# W603B.net
KiCad netlist of a schematic drawn in EAGLE
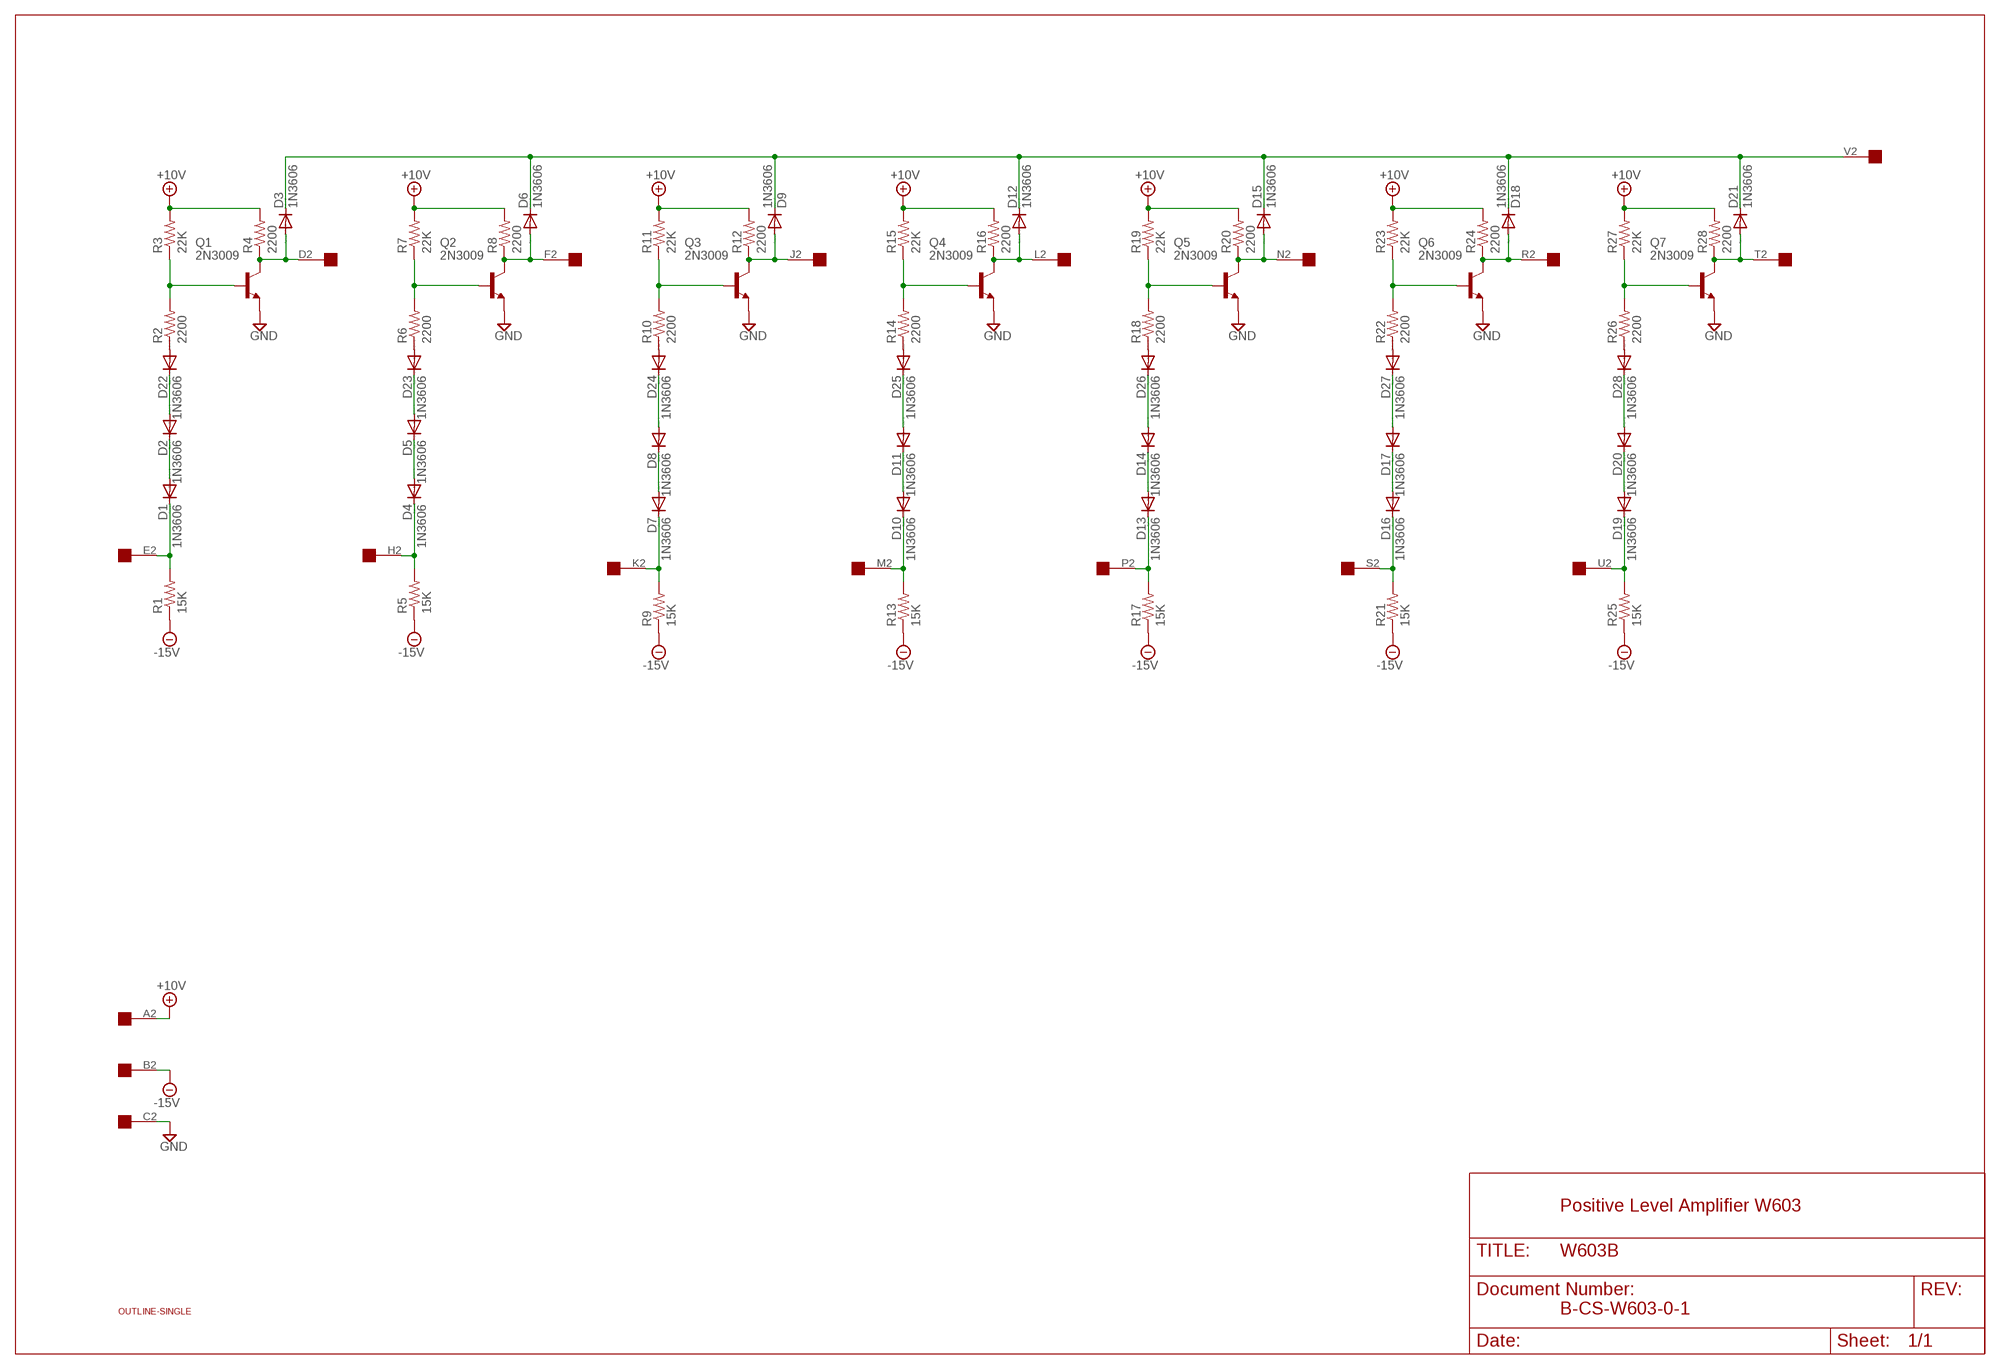
[diagram p0: schematic, sheet 1]

(export (version "E")
  (design (tool "Eeschema 10.0.6"))
  (components
    (comp (ref "D1")
      (value "1N3606")
      (footprint "eagle-import:DO35-10")
      (libsource (lib "eagle-import") (part "1N4148DO35-10"))
    )
    (comp (ref "D2")
      (value "1N3606")
      (footprint "eagle-import:DO35-10")
      (libsource (lib "eagle-import") (part "1N4148DO35-10"))
    )
    (comp (ref "D3")
      (value "1N3606")
      (footprint "eagle-import:DO35-10")
      (libsource (lib "eagle-import") (part "1N4148DO35-10"))
    )
    (comp (ref "D4")
      (value "1N3606")
      (footprint "eagle-import:DO35-10")
      (libsource (lib "eagle-import") (part "1N4148DO35-10"))
    )
    (comp (ref "D5")
      (value "1N3606")
      (footprint "eagle-import:DO35-10")
      (libsource (lib "eagle-import") (part "1N4148DO35-10"))
    )
    (comp (ref "D6")
      (value "1N3606")
      (footprint "eagle-import:DO35-10")
      (libsource (lib "eagle-import") (part "1N4148DO35-10"))
    )
    (comp (ref "D7")
      (value "1N3606")
      (footprint "eagle-import:DO35-10")
      (libsource (lib "eagle-import") (part "1N4148DO35-10"))
    )
    (comp (ref "D8")
      (value "1N3606")
      (footprint "eagle-import:DO35-10")
      (libsource (lib "eagle-import") (part "1N4148DO35-10"))
    )
    (comp (ref "D9")
      (value "1N3606")
      (footprint "eagle-import:DO35-10")
      (libsource (lib "eagle-import") (part "1N4148DO35-10"))
    )
    (comp (ref "D10")
      (value "1N3606")
      (footprint "eagle-import:DO35-10")
      (libsource (lib "eagle-import") (part "1N4148DO35-10"))
    )
    (comp (ref "D11")
      (value "1N3606")
      (footprint "eagle-import:DO35-10")
      (libsource (lib "eagle-import") (part "1N4148DO35-10"))
    )
    (comp (ref "D12")
      (value "1N3606")
      (footprint "eagle-import:DO35-10")
      (libsource (lib "eagle-import") (part "1N4148DO35-10"))
    )
    (comp (ref "D13")
      (value "1N3606")
      (footprint "eagle-import:DO35-10")
      (libsource (lib "eagle-import") (part "1N4148DO35-10"))
    )
    (comp (ref "D14")
      (value "1N3606")
      (footprint "eagle-import:DO35-10")
      (libsource (lib "eagle-import") (part "1N4148DO35-10"))
    )
    (comp (ref "D15")
      (value "1N3606")
      (footprint "eagle-import:DO35-10")
      (libsource (lib "eagle-import") (part "1N4148DO35-10"))
    )
    (comp (ref "D16")
      (value "1N3606")
      (footprint "eagle-import:DO35-10")
      (libsource (lib "eagle-import") (part "1N4148DO35-10"))
    )
    (comp (ref "D17")
      (value "1N3606")
      (footprint "eagle-import:DO35-10")
      (libsource (lib "eagle-import") (part "1N4148DO35-10"))
    )
    (comp (ref "D18")
      (value "1N3606")
      (footprint "eagle-import:DO35-10")
      (libsource (lib "eagle-import") (part "1N4148DO35-10"))
    )
    (comp (ref "D19")
      (value "1N3606")
      (footprint "eagle-import:DO35-10")
      (libsource (lib "eagle-import") (part "1N4148DO35-10"))
    )
    (comp (ref "D20")
      (value "1N3606")
      (footprint "eagle-import:DO35-10")
      (libsource (lib "eagle-import") (part "1N4148DO35-10"))
    )
    (comp (ref "D21")
      (value "1N3606")
      (footprint "eagle-import:DO35-10")
      (libsource (lib "eagle-import") (part "1N4148DO35-10"))
    )
    (comp (ref "D22")
      (value "1N3606")
      (footprint "eagle-import:DO35-10")
      (libsource (lib "eagle-import") (part "1N4148DO35-10"))
    )
    (comp (ref "D23")
      (value "1N3606")
      (footprint "eagle-import:DO35-10")
      (libsource (lib "eagle-import") (part "1N4148DO35-10"))
    )
    (comp (ref "D24")
      (value "1N3606")
      (footprint "eagle-import:DO35-10")
      (libsource (lib "eagle-import") (part "1N4148DO35-10"))
    )
    (comp (ref "D25")
      (value "1N3606")
      (footprint "eagle-import:DO35-10")
      (libsource (lib "eagle-import") (part "1N4148DO35-10"))
    )
    (comp (ref "D26")
      (value "1N3606")
      (footprint "eagle-import:DO35-10")
      (libsource (lib "eagle-import") (part "1N4148DO35-10"))
    )
    (comp (ref "D27")
      (value "1N3606")
      (footprint "eagle-import:DO35-10")
      (libsource (lib "eagle-import") (part "1N4148DO35-10"))
    )
    (comp (ref "D28")
      (value "1N3606")
      (footprint "eagle-import:DO35-10")
      (libsource (lib "eagle-import") (part "1N4148DO35-10"))
    )
    (comp (ref "Q1")
      (value "2N3009")
      (footprint "eagle-import:TO5")
      (libsource (lib "eagle-import") (part "2N2102"))
    )
    (comp (ref "Q2")
      (value "2N3009")
      (footprint "eagle-import:TO5")
      (libsource (lib "eagle-import") (part "2N2102"))
    )
    (comp (ref "Q3")
      (value "2N3009")
      (footprint "eagle-import:TO5")
      (libsource (lib "eagle-import") (part "2N2102"))
    )
    (comp (ref "Q4")
      (value "2N3009")
      (footprint "eagle-import:TO5")
      (libsource (lib "eagle-import") (part "2N2102"))
    )
    (comp (ref "Q5")
      (value "2N3009")
      (footprint "eagle-import:TO5")
      (libsource (lib "eagle-import") (part "2N2102"))
    )
    (comp (ref "Q6")
      (value "2N3009")
      (footprint "eagle-import:TO5")
      (libsource (lib "eagle-import") (part "2N2102"))
    )
    (comp (ref "Q7")
      (value "2N3009")
      (footprint "eagle-import:TO5")
      (libsource (lib "eagle-import") (part "2N2102"))
    )
    (comp (ref "R1")
      (value "15K")
      (footprint "eagle-import:0207_10")
      (libsource (lib "eagle-import") (part "R-US_0207/10"))
    )
    (comp (ref "R2")
      (value "2200")
      (footprint "eagle-import:0207_10")
      (libsource (lib "eagle-import") (part "R-US_0207/10"))
    )
    (comp (ref "R3")
      (value "22K")
      (footprint "eagle-import:0207_10")
      (libsource (lib "eagle-import") (part "R-US_0207/10"))
    )
    (comp (ref "R4")
      (value "2200")
      (footprint "eagle-import:0207_10")
      (libsource (lib "eagle-import") (part "R-US_0207/10"))
    )
    (comp (ref "R5")
      (value "15K")
      (footprint "eagle-import:0207_10")
      (libsource (lib "eagle-import") (part "R-US_0207/10"))
    )
    (comp (ref "R6")
      (value "2200")
      (footprint "eagle-import:0207_10")
      (libsource (lib "eagle-import") (part "R-US_0207/10"))
    )
    (comp (ref "R7")
      (value "22K")
      (footprint "eagle-import:0207_10")
      (libsource (lib "eagle-import") (part "R-US_0207/10"))
    )
    (comp (ref "R8")
      (value "2200")
      (footprint "eagle-import:0207_10")
      (libsource (lib "eagle-import") (part "R-US_0207/10"))
    )
    (comp (ref "R9")
      (value "15K")
      (footprint "eagle-import:0207_10")
      (libsource (lib "eagle-import") (part "R-US_0207/10"))
    )
    (comp (ref "R10")
      (value "2200")
      (footprint "eagle-import:0207_10")
      (libsource (lib "eagle-import") (part "R-US_0207/10"))
    )
    (comp (ref "R11")
      (value "22K")
      (footprint "eagle-import:0207_10")
      (libsource (lib "eagle-import") (part "R-US_0207/10"))
    )
    (comp (ref "R12")
      (value "2200")
      (footprint "eagle-import:0207_10")
      (libsource (lib "eagle-import") (part "R-US_0207/10"))
    )
    (comp (ref "R13")
      (value "15K")
      (footprint "eagle-import:0207_10")
      (libsource (lib "eagle-import") (part "R-US_0207/10"))
    )
    (comp (ref "R14")
      (value "2200")
      (footprint "eagle-import:0207_10")
      (libsource (lib "eagle-import") (part "R-US_0207/10"))
    )
    (comp (ref "R15")
      (value "22K")
      (footprint "eagle-import:0207_10")
      (libsource (lib "eagle-import") (part "R-US_0207/10"))
    )
    (comp (ref "R16")
      (value "2200")
      (footprint "eagle-import:0207_10")
      (libsource (lib "eagle-import") (part "R-US_0207/10"))
    )
    (comp (ref "R17")
      (value "15K")
      (footprint "eagle-import:0207_10")
      (libsource (lib "eagle-import") (part "R-US_0207/10"))
    )
    (comp (ref "R18")
      (value "2200")
      (footprint "eagle-import:0207_10")
      (libsource (lib "eagle-import") (part "R-US_0207/10"))
    )
    (comp (ref "R19")
      (value "22K")
      (footprint "eagle-import:0207_10")
      (libsource (lib "eagle-import") (part "R-US_0207/10"))
    )
    (comp (ref "R20")
      (value "2200")
      (footprint "eagle-import:0207_10")
      (libsource (lib "eagle-import") (part "R-US_0207/10"))
    )
    (comp (ref "R21")
      (value "15K")
      (footprint "eagle-import:0207_10")
      (libsource (lib "eagle-import") (part "R-US_0207/10"))
    )
    (comp (ref "R22")
      (value "2200")
      (footprint "eagle-import:0207_10")
      (libsource (lib "eagle-import") (part "R-US_0207/10"))
    )
    (comp (ref "R23")
      (value "22K")
      (footprint "eagle-import:0207_10")
      (libsource (lib "eagle-import") (part "R-US_0207/10"))
    )
    (comp (ref "R24")
      (value "2200")
      (footprint "eagle-import:0207_10")
      (libsource (lib "eagle-import") (part "R-US_0207/10"))
    )
    (comp (ref "R25")
      (value "15K")
      (footprint "eagle-import:0207_10")
      (libsource (lib "eagle-import") (part "R-US_0207/10"))
    )
    (comp (ref "R26")
      (value "2200")
      (footprint "eagle-import:0207_10")
      (libsource (lib "eagle-import") (part "R-US_0207/10"))
    )
    (comp (ref "R27")
      (value "22K")
      (footprint "eagle-import:0207_10")
      (libsource (lib "eagle-import") (part "R-US_0207/10"))
    )
    (comp (ref "R28")
      (value "2200")
      (footprint "eagle-import:0207_10")
      (libsource (lib "eagle-import") (part "R-US_0207/10"))
    )
    (comp (ref "U$1")
      (value "OUTLINE-SINGLE")
      (footprint "eagle-import:SINGLE")
      (libsource (lib "eagle-import") (part "OUTLINE-SINGLE"))
    )
    (comp (ref "U$2")
      (value "EDGE-1")
      (footprint "eagle-import:EDGE-CON1")
      (libsource (lib "eagle-import") (part "EDGE-1"))
    )
  )
  (nets
    (net (code "1") (name "+10V") (class "Default")
      (node (ref "R11") (pin "2") (pinfunction "2_2") (pintype "passive"))
      (node (ref "R12") (pin "2") (pinfunction "2_2") (pintype "passive"))
      (node (ref "R15") (pin "2") (pinfunction "2_2") (pintype "passive"))
      (node (ref "R16") (pin "2") (pinfunction "2_2") (pintype "passive"))
      (node (ref "R19") (pin "2") (pinfunction "2_2") (pintype "passive"))
      (node (ref "R20") (pin "2") (pinfunction "2_2") (pintype "passive"))
      (node (ref "R23") (pin "2") (pinfunction "2_2") (pintype "passive"))
      (node (ref "R24") (pin "2") (pinfunction "2_2") (pintype "passive"))
      (node (ref "R27") (pin "2") (pinfunction "2_2") (pintype "passive"))
      (node (ref "R28") (pin "2") (pinfunction "2_2") (pintype "passive"))
      (node (ref "R3") (pin "2") (pinfunction "2_2") (pintype "passive"))
      (node (ref "R4") (pin "2") (pinfunction "2_2") (pintype "passive"))
      (node (ref "R7") (pin "2") (pinfunction "2_2") (pintype "passive"))
      (node (ref "R8") (pin "2") (pinfunction "2_2") (pintype "passive"))
      (node (ref "U$2") (pin "A2") (pinfunction "1_A2") (pintype "bidirectional"))
    )
    (net (code "2") (name "-15V") (class "Default")
      (node (ref "R1") (pin "1") (pinfunction "1_1") (pintype "passive"))
      (node (ref "R13") (pin "1") (pinfunction "1_1") (pintype "passive"))
      (node (ref "R17") (pin "1") (pinfunction "1_1") (pintype "passive"))
      (node (ref "R21") (pin "1") (pinfunction "1_1") (pintype "passive"))
      (node (ref "R25") (pin "1") (pinfunction "1_1") (pintype "passive"))
      (node (ref "R5") (pin "1") (pinfunction "1_1") (pintype "passive"))
      (node (ref "R9") (pin "1") (pinfunction "1_1") (pintype "passive"))
      (node (ref "U$2") (pin "B2") (pinfunction "1_B2") (pintype "bidirectional"))
    )
    (net (code "3") (name "GND") (class "Default")
      (node (ref "Q1") (pin "1") (pinfunction "E_1") (pintype "passive"))
      (node (ref "Q2") (pin "1") (pinfunction "E_1") (pintype "passive"))
      (node (ref "Q3") (pin "1") (pinfunction "E_1") (pintype "passive"))
      (node (ref "Q4") (pin "1") (pinfunction "E_1") (pintype "passive"))
      (node (ref "Q5") (pin "1") (pinfunction "E_1") (pintype "passive"))
      (node (ref "Q6") (pin "1") (pinfunction "E_1") (pintype "passive"))
      (node (ref "Q7") (pin "1") (pinfunction "E_1") (pintype "passive"))
      (node (ref "U$2") (pin "C2") (pinfunction "1_C2") (pintype "bidirectional"))
    )
    (net (code "4") (name "Net-(D1-PadA)") (class "Default")
      (node (ref "D1") (pin "A") (pinfunction "A_A") (pintype "passive"))
      (node (ref "D2") (pin "C") (pinfunction "C_C") (pintype "passive"))
    )
    (net (code "5") (name "Net-(D2-PadA)") (class "Default")
      (node (ref "D2") (pin "A") (pinfunction "A_A") (pintype "passive"))
      (node (ref "D22") (pin "C") (pinfunction "C_C") (pintype "passive"))
    )
    (net (code "6") (name "Net-(D4-PadA)") (class "Default")
      (node (ref "D4") (pin "A") (pinfunction "A_A") (pintype "passive"))
      (node (ref "D5") (pin "C") (pinfunction "C_C") (pintype "passive"))
    )
    (net (code "7") (name "Net-(D7-PadA)") (class "Default")
      (node (ref "D7") (pin "A") (pinfunction "A_A") (pintype "passive"))
      (node (ref "D8") (pin "C") (pinfunction "C_C") (pintype "passive"))
    )
    (net (code "8") (name "Net-(D10-PadA)") (class "Default")
      (node (ref "D10") (pin "A") (pinfunction "A_A") (pintype "passive"))
      (node (ref "D11") (pin "C") (pinfunction "C_C") (pintype "passive"))
    )
    (net (code "9") (name "Net-(D11-PadA)") (class "Default")
      (node (ref "D11") (pin "A") (pinfunction "A_A") (pintype "passive"))
      (node (ref "D25") (pin "C") (pinfunction "C_C") (pintype "passive"))
    )
    (net (code "10") (name "Net-(D13-PadA)") (class "Default")
      (node (ref "D13") (pin "A") (pinfunction "A_A") (pintype "passive"))
      (node (ref "D14") (pin "C") (pinfunction "C_C") (pintype "passive"))
    )
    (net (code "11") (name "Net-(D14-PadA)") (class "Default")
      (node (ref "D14") (pin "A") (pinfunction "A_A") (pintype "passive"))
      (node (ref "D26") (pin "C") (pinfunction "C_C") (pintype "passive"))
    )
    (net (code "12") (name "Net-(D16-PadA)") (class "Default")
      (node (ref "D16") (pin "A") (pinfunction "A_A") (pintype "passive"))
      (node (ref "D17") (pin "C") (pinfunction "C_C") (pintype "passive"))
    )
    (net (code "13") (name "Net-(D17-PadA)") (class "Default")
      (node (ref "D17") (pin "A") (pinfunction "A_A") (pintype "passive"))
      (node (ref "D27") (pin "C") (pinfunction "C_C") (pintype "passive"))
    )
    (net (code "14") (name "Net-(D19-PadA)") (class "Default")
      (node (ref "D19") (pin "A") (pinfunction "A_A") (pintype "passive"))
      (node (ref "D20") (pin "C") (pinfunction "C_C") (pintype "passive"))
    )
    (net (code "15") (name "Net-(D20-PadA)") (class "Default")
      (node (ref "D20") (pin "A") (pinfunction "A_A") (pintype "passive"))
      (node (ref "D28") (pin "C") (pinfunction "C_C") (pintype "passive"))
    )
    (net (code "16") (name "Net-(D22-PadA)") (class "Default")
      (node (ref "D22") (pin "A") (pinfunction "A_A") (pintype "passive"))
      (node (ref "R2") (pin "1") (pinfunction "1_1") (pintype "passive"))
    )
    (net (code "17") (name "Net-(D23-PadA)") (class "Default")
      (node (ref "D23") (pin "A") (pinfunction "A_A") (pintype "passive"))
      (node (ref "R6") (pin "1") (pinfunction "1_1") (pintype "passive"))
    )
    (net (code "18") (name "Net-(D23-PadC)") (class "Default")
      (node (ref "D23") (pin "C") (pinfunction "C_C") (pintype "passive"))
      (node (ref "D5") (pin "A") (pinfunction "A_A") (pintype "passive"))
    )
    (net (code "19") (name "Net-(D24-PadA)") (class "Default")
      (node (ref "D24") (pin "A") (pinfunction "A_A") (pintype "passive"))
      (node (ref "R10") (pin "1") (pinfunction "1_1") (pintype "passive"))
    )
    (net (code "20") (name "Net-(D24-PadC)") (class "Default")
      (node (ref "D24") (pin "C") (pinfunction "C_C") (pintype "passive"))
      (node (ref "D8") (pin "A") (pinfunction "A_A") (pintype "passive"))
    )
    (net (code "21") (name "Net-(D25-PadA)") (class "Default")
      (node (ref "D25") (pin "A") (pinfunction "A_A") (pintype "passive"))
      (node (ref "R14") (pin "1") (pinfunction "1_1") (pintype "passive"))
    )
    (net (code "22") (name "Net-(D26-PadA)") (class "Default")
      (node (ref "D26") (pin "A") (pinfunction "A_A") (pintype "passive"))
      (node (ref "R18") (pin "1") (pinfunction "1_1") (pintype "passive"))
    )
    (net (code "23") (name "Net-(D27-PadA)") (class "Default")
      (node (ref "D27") (pin "A") (pinfunction "A_A") (pintype "passive"))
      (node (ref "R22") (pin "1") (pinfunction "1_1") (pintype "passive"))
    )
    (net (code "24") (name "Net-(D28-PadA)") (class "Default")
      (node (ref "D28") (pin "A") (pinfunction "A_A") (pintype "passive"))
      (node (ref "R26") (pin "1") (pinfunction "1_1") (pintype "passive"))
    )
    (net (code "25") (name "Net-(Q1-B)") (class "Default")
      (node (ref "Q1") (pin "2") (pinfunction "B_2") (pintype "passive"))
      (node (ref "R2") (pin "2") (pinfunction "2_2") (pintype "passive"))
      (node (ref "R3") (pin "1") (pinfunction "1_1") (pintype "passive"))
    )
    (net (code "26") (name "Net-(Q1-C)") (class "Default")
      (node (ref "D3") (pin "A") (pinfunction "A_A") (pintype "passive"))
      (node (ref "Q1") (pin "3") (pinfunction "C_3") (pintype "passive"))
      (node (ref "R4") (pin "1") (pinfunction "1_1") (pintype "passive"))
      (node (ref "U$2") (pin "D2") (pinfunction "1_D2") (pintype "bidirectional"))
    )
    (net (code "27") (name "Net-(Q2-B)") (class "Default")
      (node (ref "Q2") (pin "2") (pinfunction "B_2") (pintype "passive"))
      (node (ref "R6") (pin "2") (pinfunction "2_2") (pintype "passive"))
      (node (ref "R7") (pin "1") (pinfunction "1_1") (pintype "passive"))
    )
    (net (code "28") (name "Net-(Q2-C)") (class "Default")
      (node (ref "D6") (pin "A") (pinfunction "A_A") (pintype "passive"))
      (node (ref "Q2") (pin "3") (pinfunction "C_3") (pintype "passive"))
      (node (ref "R8") (pin "1") (pinfunction "1_1") (pintype "passive"))
      (node (ref "U$2") (pin "F2") (pinfunction "1_F2") (pintype "bidirectional"))
    )
    (net (code "29") (name "Net-(Q3-B)") (class "Default")
      (node (ref "Q3") (pin "2") (pinfunction "B_2") (pintype "passive"))
      (node (ref "R10") (pin "2") (pinfunction "2_2") (pintype "passive"))
      (node (ref "R11") (pin "1") (pinfunction "1_1") (pintype "passive"))
    )
    (net (code "30") (name "Net-(Q3-C)") (class "Default")
      (node (ref "D9") (pin "A") (pinfunction "A_A") (pintype "passive"))
      (node (ref "Q3") (pin "3") (pinfunction "C_3") (pintype "passive"))
      (node (ref "R12") (pin "1") (pinfunction "1_1") (pintype "passive"))
      (node (ref "U$2") (pin "J2") (pinfunction "1_J2") (pintype "bidirectional"))
    )
    (net (code "31") (name "Net-(Q4-B)") (class "Default")
      (node (ref "Q4") (pin "2") (pinfunction "B_2") (pintype "passive"))
      (node (ref "R14") (pin "2") (pinfunction "2_2") (pintype "passive"))
      (node (ref "R15") (pin "1") (pinfunction "1_1") (pintype "passive"))
    )
    (net (code "32") (name "Net-(Q4-C)") (class "Default")
      (node (ref "D12") (pin "A") (pinfunction "A_A") (pintype "passive"))
      (node (ref "Q4") (pin "3") (pinfunction "C_3") (pintype "passive"))
      (node (ref "R16") (pin "1") (pinfunction "1_1") (pintype "passive"))
      (node (ref "U$2") (pin "L2") (pinfunction "1_L2") (pintype "bidirectional"))
    )
    (net (code "33") (name "Net-(Q5-B)") (class "Default")
      (node (ref "Q5") (pin "2") (pinfunction "B_2") (pintype "passive"))
      (node (ref "R18") (pin "2") (pinfunction "2_2") (pintype "passive"))
      (node (ref "R19") (pin "1") (pinfunction "1_1") (pintype "passive"))
    )
    (net (code "34") (name "Net-(Q5-C)") (class "Default")
      (node (ref "D15") (pin "A") (pinfunction "A_A") (pintype "passive"))
      (node (ref "Q5") (pin "3") (pinfunction "C_3") (pintype "passive"))
      (node (ref "R20") (pin "1") (pinfunction "1_1") (pintype "passive"))
      (node (ref "U$2") (pin "N2") (pinfunction "1_N2") (pintype "bidirectional"))
    )
    (net (code "35") (name "Net-(Q6-B)") (class "Default")
      (node (ref "Q6") (pin "2") (pinfunction "B_2") (pintype "passive"))
      (node (ref "R22") (pin "2") (pinfunction "2_2") (pintype "passive"))
      (node (ref "R23") (pin "1") (pinfunction "1_1") (pintype "passive"))
    )
    (net (code "36") (name "Net-(Q6-C)") (class "Default")
      (node (ref "D18") (pin "A") (pinfunction "A_A") (pintype "passive"))
      (node (ref "Q6") (pin "3") (pinfunction "C_3") (pintype "passive"))
      (node (ref "R24") (pin "1") (pinfunction "1_1") (pintype "passive"))
      (node (ref "U$2") (pin "R2") (pinfunction "1_R2") (pintype "bidirectional"))
    )
    (net (code "37") (name "Net-(Q7-B)") (class "Default")
      (node (ref "Q7") (pin "2") (pinfunction "B_2") (pintype "passive"))
      (node (ref "R26") (pin "2") (pinfunction "2_2") (pintype "passive"))
      (node (ref "R27") (pin "1") (pinfunction "1_1") (pintype "passive"))
    )
    (net (code "38") (name "Net-(Q7-C)") (class "Default")
      (node (ref "D21") (pin "A") (pinfunction "A_A") (pintype "passive"))
      (node (ref "Q7") (pin "3") (pinfunction "C_3") (pintype "passive"))
      (node (ref "R28") (pin "1") (pinfunction "1_1") (pintype "passive"))
      (node (ref "U$2") (pin "T2") (pinfunction "1_T2") (pintype "bidirectional"))
    )
    (net (code "39") (name "Net-(U$2E-1)") (class "Default")
      (node (ref "D1") (pin "C") (pinfunction "C_C") (pintype "passive"))
      (node (ref "R1") (pin "2") (pinfunction "2_2") (pintype "passive"))
      (node (ref "U$2") (pin "E2") (pinfunction "1_E2") (pintype "bidirectional"))
    )
    (net (code "40") (name "Net-(U$2G-1)") (class "Default")
      (node (ref "D4") (pin "C") (pinfunction "C_C") (pintype "passive"))
      (node (ref "R5") (pin "2") (pinfunction "2_2") (pintype "passive"))
      (node (ref "U$2") (pin "H2") (pinfunction "1_H2") (pintype "bidirectional"))
    )
    (net (code "41") (name "Net-(U$2I-1)") (class "Default")
      (node (ref "D7") (pin "C") (pinfunction "C_C") (pintype "passive"))
      (node (ref "R9") (pin "2") (pinfunction "2_2") (pintype "passive"))
      (node (ref "U$2") (pin "K2") (pinfunction "1_K2") (pintype "bidirectional"))
    )
    (net (code "42") (name "Net-(U$2K-1)") (class "Default")
      (node (ref "D10") (pin "C") (pinfunction "C_C") (pintype "passive"))
      (node (ref "R13") (pin "2") (pinfunction "2_2") (pintype "passive"))
      (node (ref "U$2") (pin "M2") (pinfunction "1_M2") (pintype "bidirectional"))
    )
    (net (code "43") (name "Net-(U$2M-1)") (class "Default")
      (node (ref "D13") (pin "C") (pinfunction "C_C") (pintype "passive"))
      (node (ref "R17") (pin "2") (pinfunction "2_2") (pintype "passive"))
      (node (ref "U$2") (pin "P2") (pinfunction "1_P2") (pintype "bidirectional"))
    )
    (net (code "44") (name "Net-(U$2O-1)") (class "Default")
      (node (ref "D16") (pin "C") (pinfunction "C_C") (pintype "passive"))
      (node (ref "R21") (pin "2") (pinfunction "2_2") (pintype "passive"))
      (node (ref "U$2") (pin "S2") (pinfunction "1_S2") (pintype "bidirectional"))
    )
    (net (code "45") (name "Net-(U$2Q-1)") (class "Default")
      (node (ref "D19") (pin "C") (pinfunction "C_C") (pintype "passive"))
      (node (ref "R25") (pin "2") (pinfunction "2_2") (pintype "passive"))
      (node (ref "U$2") (pin "U2") (pinfunction "1_U2") (pintype "bidirectional"))
    )
    (net (code "46") (name "Net-(U$2R-1)") (class "Default")
      (node (ref "D12") (pin "C") (pinfunction "C_C") (pintype "passive"))
      (node (ref "D15") (pin "C") (pinfunction "C_C") (pintype "passive"))
      (node (ref "D18") (pin "C") (pinfunction "C_C") (pintype "passive"))
      (node (ref "D21") (pin "C") (pinfunction "C_C") (pintype "passive"))
      (node (ref "D3") (pin "C") (pinfunction "C_C") (pintype "passive"))
      (node (ref "D6") (pin "C") (pinfunction "C_C") (pintype "passive"))
      (node (ref "D9") (pin "C") (pinfunction "C_C") (pintype "passive"))
      (node (ref "U$2") (pin "V2") (pinfunction "1_V2") (pintype "bidirectional"))
    )
  )
)
